# RF.net
KiCad netlist of a schematic drawn in Altium Designer
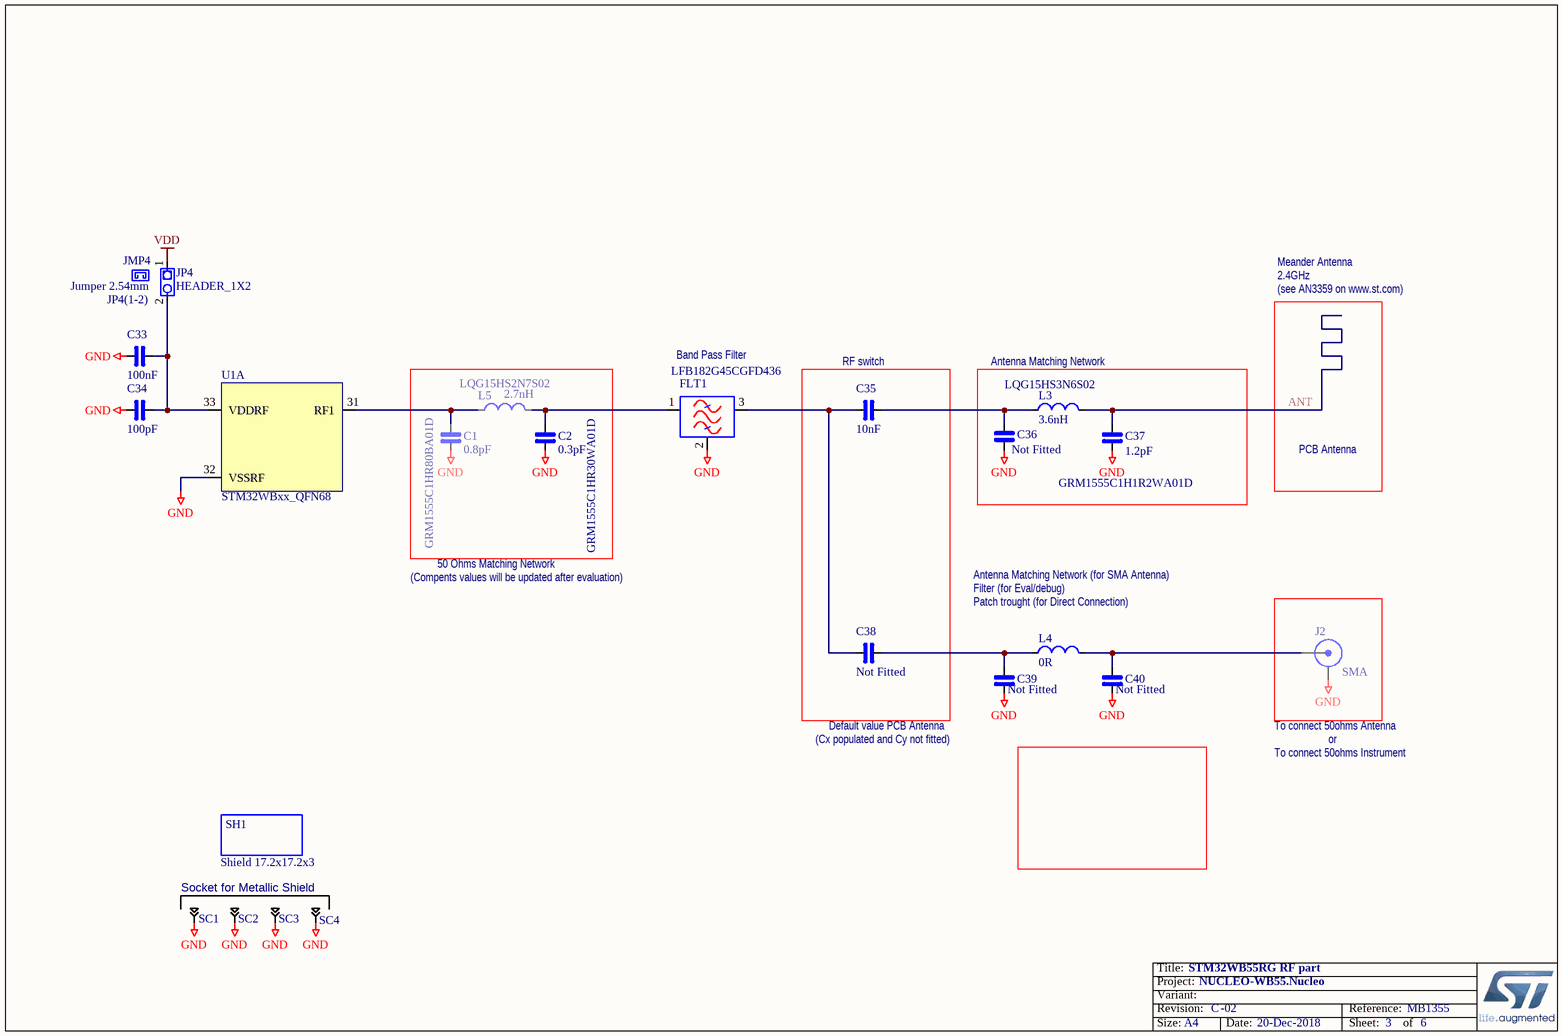
[diagram p0: RF.SchDoc]

(export (version "E")
  (design (tool "Eeschema 10.0.6"))
  (components
    (comp (ref "C1")
      (value "0.8pF")
      (footprint "0402_CAP_NPOL")
      (description "Capacitor_not polarized")
      (fields (field (name "REF") "GRM1555C1HR80BA01D"))
      (libsource (lib "Passive") (part "CAP_NPOL"))
    )
    (comp (ref "C2")
      (value "0.3pF")
      (footprint "0402_CAP_NPOL")
      (description "Capacitor_not polarized")
      (fields (field (name "REF") "GRM1555C1HR30WA01D"))
      (libsource (lib "Passive") (part "CAP_NPOL"))
    )
    (comp (ref "C33")
      (value "100nF")
      (footprint "0402_CAP_NPOL")
      (description "Capacitor_not polarized")
      (libsource (lib "ST_Lib3D") (part "CAP_NPOL"))
    )
    (comp (ref "C34")
      (value "100pF")
      (footprint "0402_CAP_NPOL")
      (description "Capacitor_not polarized")
      (libsource (lib "ST_Lib3D") (part "CAP_NPOL"))
    )
    (comp (ref "C35")
      (value "10nF")
      (footprint "0402_CAP_NPOL")
      (description "Capacitor_not polarized")
      (libsource (lib "ST_Lib3D") (part "CAP_NPOL"))
    )
    (comp (ref "C36")
      (value "~")
      (footprint "0402_CAP_NPOL")
      (description "Capacitor_not polarized")
      (fields (field (name "FITTED") "Not Fitted"))
      (libsource (lib "ST_Lib3D") (part "CAP_NPOL"))
    )
    (comp (ref "C37")
      (value "1.2pF")
      (footprint "0402_CAP_NPOL")
      (description "Capacitor_not polarized")
      (fields (field (name "REF") "GRM1555C1H1R2WA01D"))
      (libsource (lib "ST_Lib3D") (part "CAP_NPOL"))
    )
    (comp (ref "C38")
      (value "~")
      (footprint "0402_CAP_NPOL")
      (description "Capacitor_not polarized")
      (fields (field (name "FITTED") "Not Fitted"))
      (libsource (lib "ST_Lib3D") (part "CAP_NPOL"))
    )
    (comp (ref "C39")
      (value "~")
      (footprint "0402_CAP_NPOL")
      (description "Capacitor_not polarized")
      (fields (field (name "FITTED") "Not Fitted"))
      (libsource (lib "ST_Lib3D") (part "CAP_NPOL"))
    )
    (comp (ref "C40")
      (value "~")
      (footprint "0402_CAP_NPOL")
      (description "Capacitor_not polarized")
      (fields (field (name "FITTED") "Not Fitted"))
      (libsource (lib "ST_Lib3D") (part "CAP_NPOL"))
    )
    (comp (ref "FLT1")
      (value "LFB182G45CGFD436")
      (footprint "LFB182G45CGFD436")
      (description "Band Pass Filter Murata LFB182G45CGFD436")
      (libsource (lib "Passive") (part "LFB182G45CGFD436"))
    )
    (comp (ref "J2") (value "SMA") (footprint "SMA_T_9.52_NF") (libsource (lib "RF connector") (part "SMA")))
    (comp (ref "JMP4")
      (value "Jumper 2.54mm")
      (footprint "Jumper 2.54mm BLACK")
      (fields (field (name "DEFAULT") "JP4(1-2)"))
      (libsource (lib "Connector") (part "Jumper 2.54mm"))
    )
    (comp (ref "JP4")
      (value "HEADER_1X2")
      (footprint "Header M 1x2x2.54 TH V")
      (libsource (lib "Connector") (part "HEADER_1X2_L"))
    )
    (comp (ref "L3")
      (value "3.6nH")
      (footprint "0402_COIL")
      (fields (field (name "REF") "LQG15HS3N6S02"))
      (libsource (lib "Passive") (part "INDUCTOR_SMD_STDL"))
    )
    (comp (ref "L4")
      (value "0R")
      (footprint "0402_COIL")
      (libsource (lib "Passive") (part "INDUCTOR_SMD_STDL"))
    )
    (comp (ref "L5")
      (value "2.7nH")
      (footprint "0402_COIL")
      (fields (field (name "REF") "LQG15HS2N7S02"))
      (libsource (lib "Passive") (part "INDUCTOR_SMD_STDL"))
    )
    (comp (ref "SC1")
      (value "Shield Clip_A 3.9x1.1x1.28")
      (footprint "Shield Clip_A 3.9x1.1x1.28")
      (description "Harwin S0951-46R")
      (libsource (lib "Box_Meca") (part "Shield Clip_A 3.9x1.1x1.28"))
    )
    (comp (ref "SC2")
      (value "Shield Clip_A 3.9x1.1x1.28")
      (footprint "Shield Clip_A 3.9x1.1x1.28")
      (description "Harwin S0951-46R")
      (libsource (lib "Box_Meca") (part "Shield Clip_A 3.9x1.1x1.28"))
    )
    (comp (ref "SC3")
      (value "Shield Clip_A 3.9x1.1x1.28")
      (footprint "Shield Clip_A 3.9x1.1x1.28")
      (description "Harwin S0951-46R")
      (libsource (lib "Box_Meca") (part "Shield Clip_A 3.9x1.1x1.28"))
    )
    (comp (ref "SC4")
      (value "Shield Clip_A 3.9x1.1x1.28")
      (footprint "Shield Clip_A 3.9x1.1x1.28")
      (description "Harwin S0951-46R")
      (libsource (lib "Box_Meca") (part "Shield Clip_A 3.9x1.1x1.28"))
    )
    (comp (ref "SH1")
      (value "Shield 17.2x17.2x3")
      (footprint "Shield 17.2x17.2x3")
      (description "Shield")
      (libsource (lib "Box_Meca") (part "Shield"))
    )
    (comp (ref "U1")
      (value "STM32WBxx_QFN68")
      (footprint "VFQFPN68_8x8x0.1_p0.4")
      (libsource (lib "Active") (part "STM32WBxx_QFN68"))
    )
  )
  (nets
    (net (code "1") (name "/ANT") (class "Default")
      (node (ref "C37") (pin "2") (pinfunction "2_2") (pintype "passive"))
      (node (ref "L3") (pin "2") (pinfunction "2_2") (pintype "passive"))
    )
    (net (code "2") (name "GND") (class "Default")
      (node (ref "C1") (pin "1") (pinfunction "1_1") (pintype "passive"))
      (node (ref "C2") (pin "1") (pinfunction "1_1") (pintype "passive"))
      (node (ref "C33") (pin "1") (pinfunction "1_1") (pintype "passive"))
      (node (ref "C34") (pin "1") (pinfunction "1_1") (pintype "passive"))
      (node (ref "C36") (pin "2") (pinfunction "2_2") (pintype "passive"))
      (node (ref "C37") (pin "1") (pinfunction "1_1") (pintype "passive"))
      (node (ref "C39") (pin "1") (pinfunction "1_1") (pintype "passive"))
      (node (ref "C40") (pin "1") (pinfunction "1_1") (pintype "passive"))
      (node (ref "FLT1") (pin "2") (pinfunction "GND_2") (pintype "passive"))
      (node (ref "J2") (pin "2") (pinfunction "Y_2") (pintype "passive"))
      (node (ref "SC1") (pin "1") (pinfunction "1_1") (pintype "passive"))
      (node (ref "SC2") (pin "1") (pinfunction "1_1") (pintype "passive"))
      (node (ref "SC3") (pin "1") (pinfunction "1_1") (pintype "passive"))
      (node (ref "SC4") (pin "1") (pinfunction "1_1") (pintype "passive"))
      (node (ref "U1") (pin "32") (pinfunction "VSSRF_32") (pintype "passive"))
    )
    (net (code "3") (name "Net-(C2-Pad2)") (class "Default")
      (node (ref "C2") (pin "2") (pinfunction "2_2") (pintype "passive"))
      (node (ref "FLT1") (pin "1") (pinfunction "I/O_1") (pintype "passive"))
      (node (ref "L5") (pin "2") (pinfunction "2_2") (pintype "passive"))
    )
    (net (code "4") (name "Net-(C35-Pad1)") (class "Default")
      (node (ref "C35") (pin "1") (pinfunction "1_1") (pintype "passive"))
      (node (ref "C38") (pin "1") (pinfunction "1_1") (pintype "passive"))
      (node (ref "FLT1") (pin "3") (pinfunction "I/O_3") (pintype "passive"))
    )
    (net (code "5") (name "Net-(C35-Pad2)") (class "Default")
      (node (ref "C35") (pin "2") (pinfunction "2_2") (pintype "passive"))
      (node (ref "C36") (pin "1") (pinfunction "1_1") (pintype "passive"))
      (node (ref "L3") (pin "1") (pinfunction "1_1") (pintype "passive"))
    )
    (net (code "6") (name "Net-(C38-Pad2)") (class "Default")
      (node (ref "C38") (pin "2") (pinfunction "2_2") (pintype "passive"))
      (node (ref "C39") (pin "2") (pinfunction "2_2") (pintype "passive"))
      (node (ref "L4") (pin "1") (pinfunction "1_1") (pintype "passive"))
    )
    (net (code "7") (name "Net-(J2-X)") (class "Default")
      (node (ref "C40") (pin "2") (pinfunction "2_2") (pintype "passive"))
      (node (ref "J2") (pin "1") (pinfunction "X_1") (pintype "passive"))
      (node (ref "L4") (pin "2") (pinfunction "2_2") (pintype "passive"))
    )
    (net (code "8") (name "Net-(U1A-RF1)") (class "Default")
      (node (ref "C1") (pin "2") (pinfunction "2_2") (pintype "passive"))
      (node (ref "L5") (pin "1") (pinfunction "1_1") (pintype "passive"))
      (node (ref "U1") (pin "31") (pinfunction "RF1_31") (pintype "passive"))
    )
    (net (code "9") (name "Net-(U1A-VDDRF)") (class "Default")
      (node (ref "C33") (pin "2") (pinfunction "2_2") (pintype "passive"))
      (node (ref "C34") (pin "2") (pinfunction "2_2") (pintype "passive"))
      (node (ref "JP4") (pin "2") (pinfunction "2_2") (pintype "passive"))
      (node (ref "U1") (pin "33") (pinfunction "VDDRF_33") (pintype "passive"))
    )
    (net (code "10") (name "VDD") (class "Default")
      (node (ref "JP4") (pin "1") (pinfunction "1_1") (pintype "passive"))
    )
  )
)
